# main_board.net
KiCad netlist of a schematic drawn in EAGLE
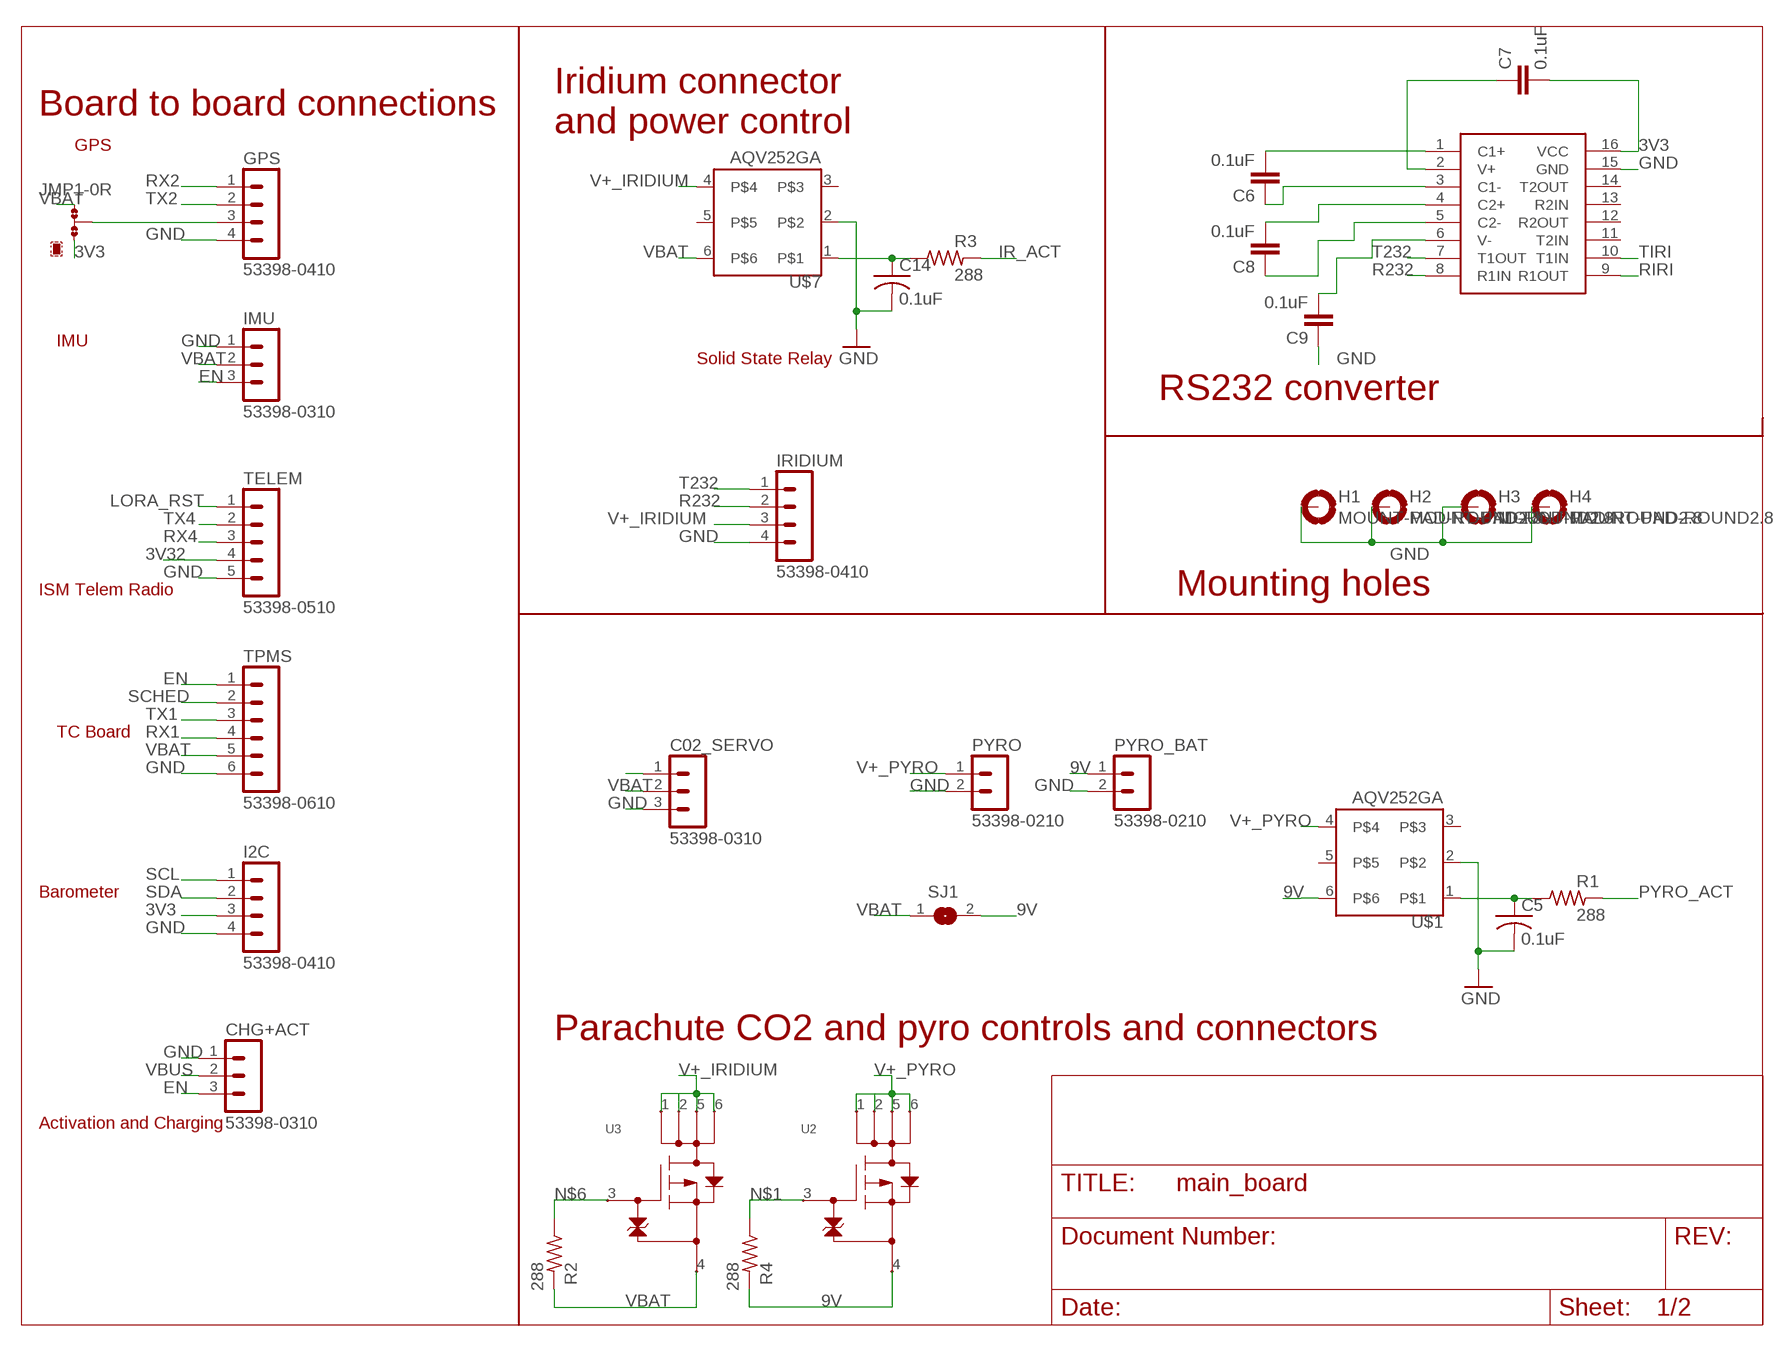
[diagram p0: schematic, sheet 1]
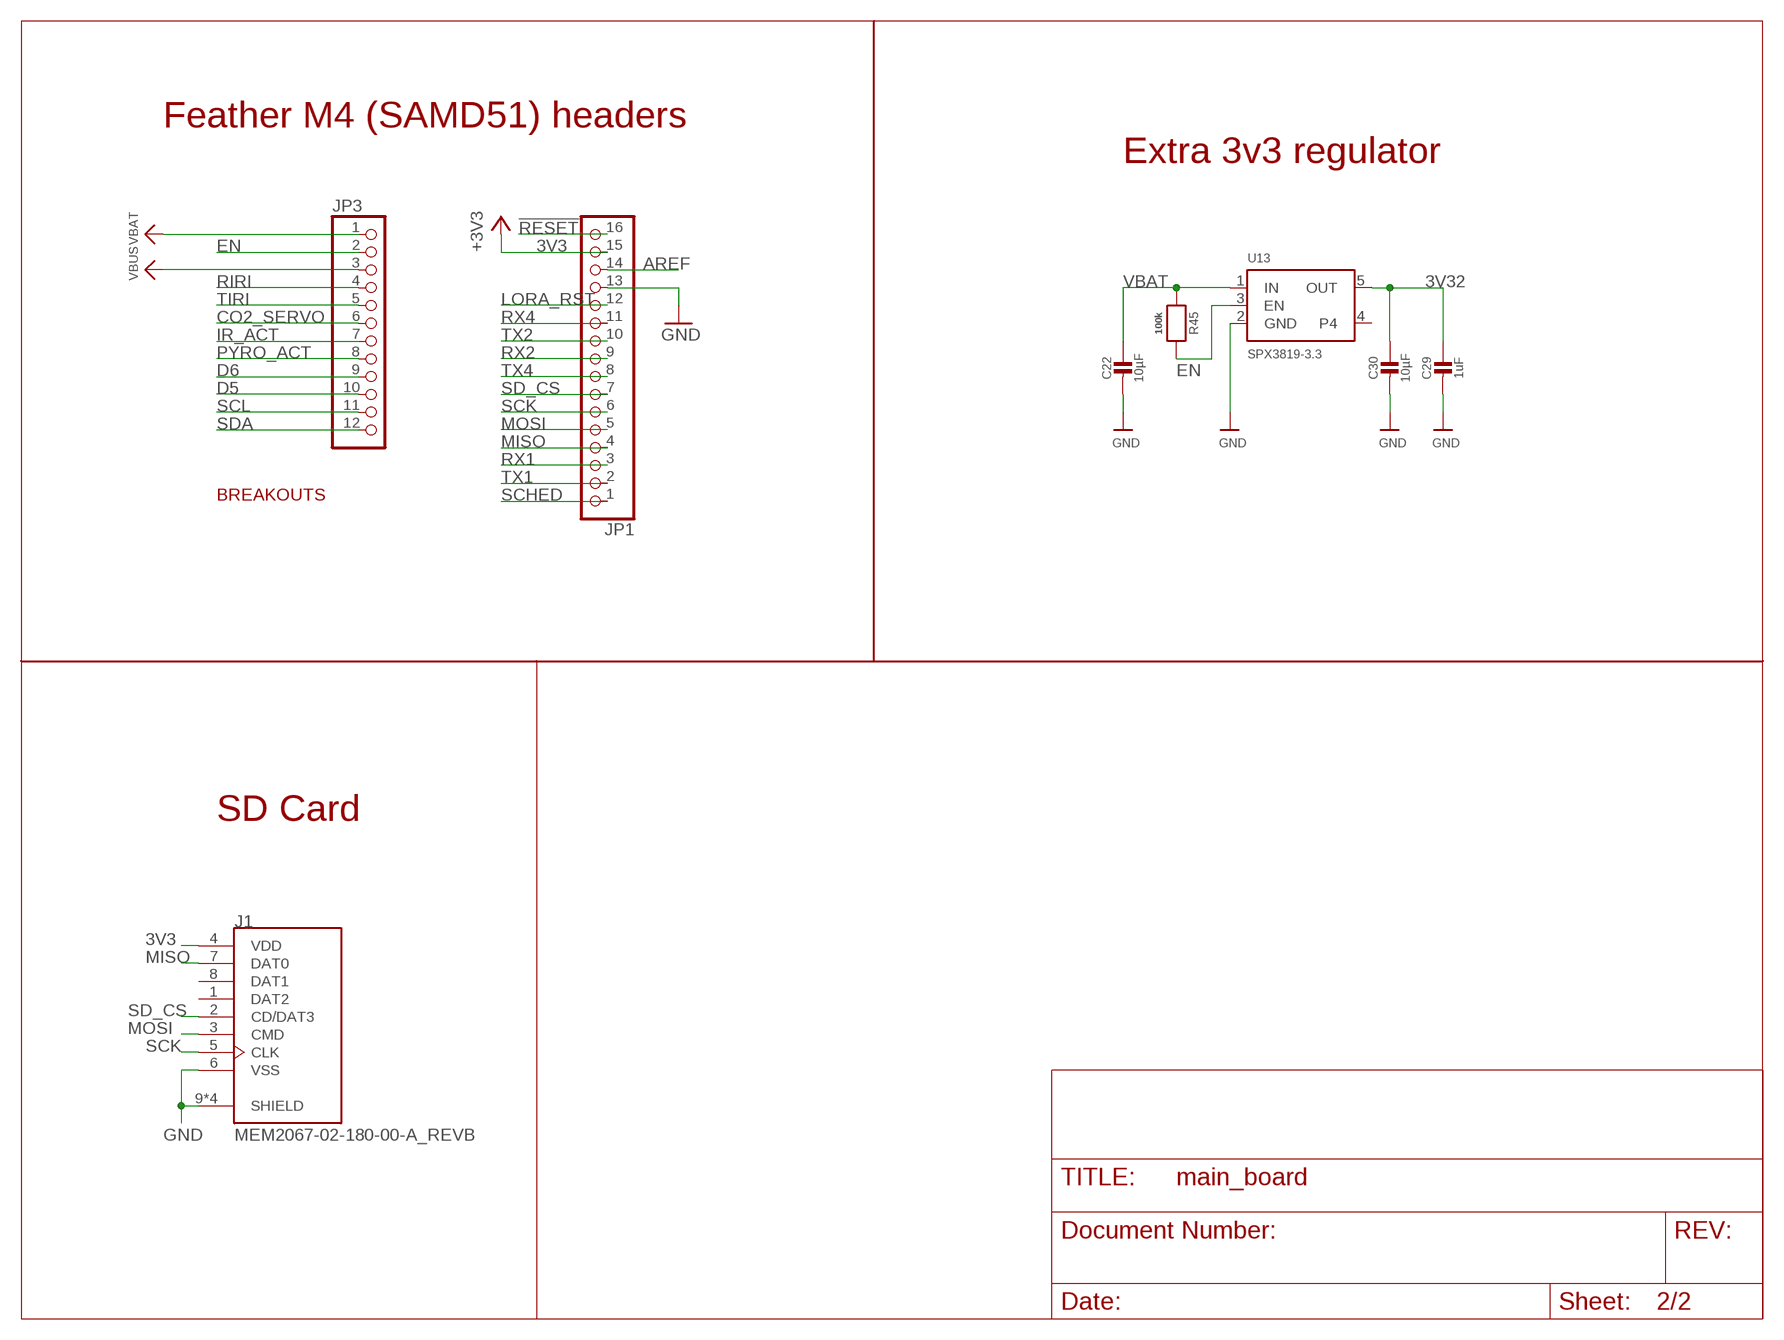
[diagram p1: schematic, sheet 2]

(export (version "E")
  (design (tool "Eeschema 10.0.6"))
  (components
    (comp (ref "C22")
      (value "10µF")
      (footprint "eagle-import:0805-NO")
      (libsource (lib "eagle-import") (part "CAP_CERAMIC0805-NOOUTLINE"))
    )
    (comp (ref "C29")
      (value "1uF")
      (footprint "eagle-import:0603-NO")
      (libsource (lib "eagle-import") (part "CAP_CERAMIC0603_NO"))
    )
    (comp (ref "C30")
      (value "10µF")
      (footprint "eagle-import:0805-NO")
      (libsource (lib "eagle-import") (part "CAP_CERAMIC0805-NOOUTLINE"))
    )
    (comp (ref "J1")
      (value "MEM2067-02-180-00-A_REVB")
      (footprint "eagle-import:GCT_MEM2067-02-180-00-A_REVB")
      (fields (field (name "MF") "Global Connector Technology") (field (name "MP") "MEM2067-02-180-00-A"))
      (libsource (lib "eagle-import") (part "MEM2067-02-180-00-A_REVB"))
    )
    (comp (ref "JP1")
      (value "HEADER-1X16ROUND")
      (footprint "eagle-import:1X16_ROUND")
      (libsource (lib "eagle-import") (part "HEADER-1X16ROUND"))
    )
    (comp (ref "JP3")
      (value "HEADER-1X12")
      (footprint "eagle-import:1X12_ROUND")
      (libsource (lib "eagle-import") (part "HEADER-1X12"))
    )
    (comp (ref "R45")
      (value "100k")
      (footprint "eagle-import:0603-NO")
      (libsource (lib "eagle-import") (part "RESISTOR_0603_NOOUT"))
    )
    (comp (ref "U13")
      (value "SPX3819-3.3")
      (footprint "eagle-import:SOT23-5")
      (libsource (lib "eagle-import") (part "VREG_SOT23-5"))
    )
    (comp (ref "C02_SERVO")
      (value "53398-0310")
      (footprint "eagle-import:53398-0310")
      (libsource (lib "eagle-import") (part "53398-0310"))
    )
    (comp (ref "C5")
      (value "0.1uF")
      (footprint "eagle-import:C0603")
      (libsource (lib "eagle-import") (part "C-USC0603"))
    )
    (comp (ref "C6")
      (value "0.1uF")
      (footprint "eagle-import:C0603")
      (libsource (lib "eagle-import") (part "C-EUC0603"))
    )
    (comp (ref "C7")
      (value "0.1uF")
      (footprint "eagle-import:C0603")
      (libsource (lib "eagle-import") (part "C-EUC0603"))
    )
    (comp (ref "C8")
      (value "0.1uF")
      (footprint "eagle-import:C0603")
      (libsource (lib "eagle-import") (part "C-EUC0603"))
    )
    (comp (ref "C9")
      (value "0.1uF")
      (footprint "eagle-import:C0603")
      (libsource (lib "eagle-import") (part "C-EUC0603"))
    )
    (comp (ref "C14")
      (value "0.1uF")
      (footprint "eagle-import:C0603")
      (libsource (lib "eagle-import") (part "C-USC0603"))
    )
    (comp (ref "CHG+ACT")
      (value "53398-0310")
      (footprint "eagle-import:53398-0310")
      (libsource (lib "eagle-import") (part "53398-0310"))
    )
    (comp (ref "GPS")
      (value "53398-0410")
      (footprint "eagle-import:53398-0410")
      (libsource (lib "eagle-import") (part "53398-0410"))
    )
    (comp (ref "H1")
      (value "MOUNT-PAD-ROUND2.8")
      (footprint "eagle-import:2,8-PAD")
      (libsource (lib "eagle-import") (part "MOUNT-PAD-ROUND2.8"))
    )
    (comp (ref "H2")
      (value "MOUNT-PAD-ROUND2.8")
      (footprint "eagle-import:2,8-PAD")
      (libsource (lib "eagle-import") (part "MOUNT-PAD-ROUND2.8"))
    )
    (comp (ref "H3")
      (value "MOUNT-PAD-ROUND2.8")
      (footprint "eagle-import:2,8-PAD")
      (libsource (lib "eagle-import") (part "MOUNT-PAD-ROUND2.8"))
    )
    (comp (ref "H4")
      (value "MOUNT-PAD-ROUND2.8")
      (footprint "eagle-import:2,8-PAD")
      (libsource (lib "eagle-import") (part "MOUNT-PAD-ROUND2.8"))
    )
    (comp (ref "I2C")
      (value "53398-0410")
      (footprint "eagle-import:53398-0410")
      (libsource (lib "eagle-import") (part "53398-0410"))
    )
    (comp (ref "IMU")
      (value "53398-0310")
      (footprint "eagle-import:53398-0310")
      (libsource (lib "eagle-import") (part "53398-0310"))
    )
    (comp (ref "IRIDIUM")
      (value "53398-0410")
      (footprint "eagle-import:53398-0410")
      (libsource (lib "eagle-import") (part "53398-0410"))
    )
    (comp (ref "JMP1")
      (value "0R-JUMPA")
      (footprint "eagle-import:A0R-JMP")
      (libsource (lib "eagle-import") (part "0R-JUMPA"))
    )
    (comp (ref "PYRO")
      (value "53398-0210")
      (footprint "eagle-import:53398-0210")
      (libsource (lib "eagle-import") (part "53398-0210"))
    )
    (comp (ref "PYRO_BAT")
      (value "53398-0210")
      (footprint "eagle-import:53398-0210")
      (libsource (lib "eagle-import") (part "53398-0210"))
    )
    (comp (ref "R1")
      (value "288")
      (footprint "eagle-import:R0603")
      (libsource (lib "eagle-import") (part "R-US_R0603"))
    )
    (comp (ref "R2")
      (value "288")
      (footprint "eagle-import:R0603")
      (libsource (lib "eagle-import") (part "R-US_R0603"))
    )
    (comp (ref "R3")
      (value "288")
      (footprint "eagle-import:R0603")
      (libsource (lib "eagle-import") (part "R-US_R0603"))
    )
    (comp (ref "R4")
      (value "288")
      (footprint "eagle-import:R0603")
      (libsource (lib "eagle-import") (part "R-US_R0603"))
    )
    (comp (ref "SJ1") (value "SJ") (footprint "eagle-import:SJ") (libsource (lib "eagle-import") (part "SJ")))
    (comp (ref "TELEM")
      (value "53398-0510")
      (footprint "eagle-import:53398-0510")
      (libsource (lib "eagle-import") (part "53398-0510"))
    )
    (comp (ref "TPMS")
      (value "53398-0610")
      (footprint "eagle-import:53398-0610")
      (libsource (lib "eagle-import") (part "53398-0610"))
    )
    (comp (ref "U$1")
      (value "AQV252GA")
      (footprint "eagle-import:DIP6")
      (libsource (lib "eagle-import") (part "AQV252GA"))
    )
    (comp (ref "U$2")
      (value "UM3232EEAE")
      (footprint "eagle-import:RQ_16_ADI")
      (libsource (lib "eagle-import") (part "UM3232EEAE"))
    )
    (comp (ref "U$7")
      (value "AQV252GA")
      (footprint "eagle-import:DIP6")
      (libsource (lib "eagle-import") (part "AQV252GA"))
    )
    (comp (ref "U2")
      (value "SSM6J414TU")
      (footprint "eagle-import:UF6_TOS")
      (fields (field (name "COPYRIGHT") "Copyright (C) 2021 Ultra Librarian. All rights reserved."))
      (libsource (lib "eagle-import") (part "SSM6J414TU"))
    )
    (comp (ref "U3")
      (value "SSM6J414TU")
      (footprint "eagle-import:UF6_TOS")
      (fields (field (name "COPYRIGHT") "Copyright (C) 2021 Ultra Librarian. All rights reserved."))
      (libsource (lib "eagle-import") (part "SSM6J414TU"))
    )
  )
  (nets
    (net (code "1") (name "3V3") (class "Default")
      (node (ref "C7") (pin "2") (pinfunction "2_2") (pintype "passive"))
      (node (ref "I2C") (pin "3") (pinfunction "3_3") (pintype "passive"))
      (node (ref "J1") (pin "4") (pinfunction "VDD_4") (pintype "power_in"))
      (node (ref "JMP1") (pin "3") (pinfunction "3_3") (pintype "passive"))
      (node (ref "JP1") (pin "15") (pinfunction "15_15") (pintype "passive"))
      (node (ref "U$2") (pin "16") (pinfunction "VCC_16") (pintype "bidirectional"))
    )
    (net (code "2") (name "3V32") (class "Default")
      (node (ref "C29") (pin "1") (pinfunction "1_1") (pintype "passive"))
      (node (ref "C30") (pin "1") (pinfunction "1_1") (pintype "passive"))
      (node (ref "TELEM") (pin "4") (pinfunction "4_4") (pintype "passive"))
      (node (ref "U13") (pin "5") (pinfunction "OUT_5") (pintype "power_in"))
    )
    (net (code "3") (name "9V") (class "Default")
      (node (ref "PYRO_BAT") (pin "1") (pinfunction "1_1") (pintype "passive"))
      (node (ref "R4") (pin "2") (pinfunction "2_2") (pintype "passive"))
      (node (ref "SJ1") (pin "2") (pinfunction "2_2") (pintype "passive"))
      (node (ref "U$1") (pin "6") (pinfunction "P$6_6") (pintype "bidirectional"))
      (node (ref "U2") (pin "4") (pinfunction "4_4") (pintype "passive"))
    )
    (net (code "4") (name "AREF") (class "Default")
      (node (ref "JP1") (pin "14") (pinfunction "14_14") (pintype "passive"))
    )
    (net (code "5") (name "CO2_SERVO") (class "Default")
      (node (ref "C02_SERVO") (pin "1") (pinfunction "1_1") (pintype "passive"))
      (node (ref "JP3") (pin "6") (pinfunction "6_6") (pintype "passive"))
    )
    (net (code "6") (name "D5") (class "Default")
      (node (ref "JP3") (pin "10") (pinfunction "10_10") (pintype "passive"))
    )
    (net (code "7") (name "D6") (class "Default")
      (node (ref "JP3") (pin "9") (pinfunction "9_9") (pintype "passive"))
    )
    (net (code "8") (name "EN") (class "Default")
      (node (ref "CHG+ACT") (pin "3") (pinfunction "3_3") (pintype "passive"))
      (node (ref "IMU") (pin "3") (pinfunction "3_3") (pintype "passive"))
      (node (ref "JP3") (pin "2") (pinfunction "2_2") (pintype "passive"))
      (node (ref "R45") (pin "2") (pinfunction "2_2") (pintype "passive"))
      (node (ref "TPMS") (pin "1") (pinfunction "1_1") (pintype "passive"))
      (node (ref "U13") (pin "3") (pinfunction "EN_3") (pintype "input"))
    )
    (net (code "9") (name "GND") (class "Default")
      (node (ref "C02_SERVO") (pin "3") (pinfunction "3_3") (pintype "passive"))
      (node (ref "C14") (pin "2") (pinfunction "2_2") (pintype "passive"))
      (node (ref "C22") (pin "2") (pinfunction "2_2") (pintype "passive"))
      (node (ref "C29") (pin "2") (pinfunction "2_2") (pintype "passive"))
      (node (ref "C30") (pin "2") (pinfunction "2_2") (pintype "passive"))
      (node (ref "C5") (pin "2") (pinfunction "2_2") (pintype "passive"))
      (node (ref "C9") (pin "1") (pinfunction "1_1") (pintype "passive"))
      (node (ref "CHG+ACT") (pin "1") (pinfunction "1_1") (pintype "passive"))
      (node (ref "GPS") (pin "4") (pinfunction "4_4") (pintype "passive"))
      (node (ref "H1") (pin "B2,8") (pinfunction "MOUNT_B2,8") (pintype "passive"))
      (node (ref "H2") (pin "B2,8") (pinfunction "MOUNT_B2,8") (pintype "passive"))
      (node (ref "H3") (pin "B2,8") (pinfunction "MOUNT_B2,8") (pintype "passive"))
      (node (ref "H4") (pin "B2,8") (pinfunction "MOUNT_B2,8") (pintype "passive"))
      (node (ref "I2C") (pin "4") (pinfunction "4_4") (pintype "passive"))
      (node (ref "IMU") (pin "1") (pinfunction "1_1") (pintype "passive"))
      (node (ref "IRIDIUM") (pin "4") (pinfunction "4_4") (pintype "passive"))
      (node (ref "J1") (pin "10") (pinfunction "SHIELD_10") (pintype "passive"))
      (node (ref "J1") (pin "11") (pinfunction "SHIELD_11") (pintype "passive"))
      (node (ref "J1") (pin "12") (pinfunction "SHIELD_12") (pintype "passive"))
      (node (ref "J1") (pin "6") (pinfunction "VSS_6") (pintype "power_in"))
      (node (ref "J1") (pin "9") (pinfunction "SHIELD_9") (pintype "passive"))
      (node (ref "JP1") (pin "13") (pinfunction "13_13") (pintype "passive"))
      (node (ref "PYRO") (pin "2") (pinfunction "2_2") (pintype "passive"))
      (node (ref "PYRO_BAT") (pin "2") (pinfunction "2_2") (pintype "passive"))
      (node (ref "TELEM") (pin "5") (pinfunction "5_5") (pintype "passive"))
      (node (ref "TPMS") (pin "6") (pinfunction "6_6") (pintype "passive"))
      (node (ref "U$1") (pin "2") (pinfunction "P$2_2") (pintype "bidirectional"))
      (node (ref "U$2") (pin "15") (pinfunction "GND_15") (pintype "bidirectional"))
      (node (ref "U$7") (pin "2") (pinfunction "P$2_2") (pintype "bidirectional"))
      (node (ref "U13") (pin "2") (pinfunction "GND_2") (pintype "power_in"))
    )
    (net (code "10") (name "IR_ACT") (class "Default")
      (node (ref "JP3") (pin "7") (pinfunction "7_7") (pintype "passive"))
      (node (ref "R3") (pin "2") (pinfunction "2_2") (pintype "passive"))
    )
    (net (code "11") (name "LORA_RST") (class "Default")
      (node (ref "JP1") (pin "12") (pinfunction "12_12") (pintype "passive"))
      (node (ref "TELEM") (pin "1") (pinfunction "1_1") (pintype "passive"))
    )
    (net (code "12") (name "MISO") (class "Default")
      (node (ref "J1") (pin "7") (pinfunction "DAT0_7") (pintype "bidirectional"))
      (node (ref "JP1") (pin "4") (pinfunction "4_4") (pintype "passive"))
    )
    (net (code "13") (name "MOSI") (class "Default")
      (node (ref "J1") (pin "3") (pinfunction "CMD_3") (pintype "bidirectional"))
      (node (ref "JP1") (pin "5") (pinfunction "5_5") (pintype "passive"))
    )
    (net (code "14") (name "N$1") (class "Default")
      (node (ref "C5") (pin "1") (pinfunction "1_1") (pintype "passive"))
      (node (ref "R1") (pin "1") (pinfunction "1_1") (pintype "passive"))
      (node (ref "R4") (pin "1") (pinfunction "1_1") (pintype "passive"))
      (node (ref "U$1") (pin "1") (pinfunction "P$1_1") (pintype "bidirectional"))
      (node (ref "U2") (pin "3") (pinfunction "3_3") (pintype "passive"))
    )
    (net (code "15") (name "N$6") (class "Default")
      (node (ref "C14") (pin "1") (pinfunction "1_1") (pintype "passive"))
      (node (ref "R2") (pin "1") (pinfunction "1_1") (pintype "passive"))
      (node (ref "R3") (pin "1") (pinfunction "1_1") (pintype "passive"))
      (node (ref "U$7") (pin "1") (pinfunction "P$1_1") (pintype "bidirectional"))
      (node (ref "U3") (pin "3") (pinfunction "3_3") (pintype "passive"))
    )
    (net (code "16") (name "Net-(GPS-Pad3)") (class "Default")
      (node (ref "GPS") (pin "3") (pinfunction "3_3") (pintype "passive"))
      (node (ref "JMP1") (pin "2") (pinfunction "2_2") (pintype "passive"))
    )
    (net (code "17") (name "Net-(U$2-C1+)") (class "Default")
      (node (ref "C6") (pin "2") (pinfunction "2_2") (pintype "passive"))
      (node (ref "U$2") (pin "1") (pinfunction "C1+_1") (pintype "bidirectional"))
    )
    (net (code "18") (name "Net-(U$2-C1-)") (class "Default")
      (node (ref "C6") (pin "1") (pinfunction "1_1") (pintype "passive"))
      (node (ref "U$2") (pin "3") (pinfunction "C1-_3") (pintype "bidirectional"))
    )
    (net (code "19") (name "Net-(U$2-C2+)") (class "Default")
      (node (ref "C8") (pin "2") (pinfunction "2_2") (pintype "passive"))
      (node (ref "U$2") (pin "4") (pinfunction "C2+_4") (pintype "bidirectional"))
    )
    (net (code "20") (name "Net-(U$2-C2-)") (class "Default")
      (node (ref "C8") (pin "1") (pinfunction "1_1") (pintype "passive"))
      (node (ref "U$2") (pin "5") (pinfunction "C2-_5") (pintype "bidirectional"))
    )
    (net (code "21") (name "Net-(U$2-V+)") (class "Default")
      (node (ref "C7") (pin "1") (pinfunction "1_1") (pintype "passive"))
      (node (ref "U$2") (pin "2") (pinfunction "V+_2") (pintype "bidirectional"))
    )
    (net (code "22") (name "Net-(U$2-V-)") (class "Default")
      (node (ref "C9") (pin "2") (pinfunction "2_2") (pintype "passive"))
      (node (ref "U$2") (pin "6") (pinfunction "V-_6") (pintype "bidirectional"))
    )
    (net (code "23") (name "PYRO_ACT") (class "Default")
      (node (ref "JP3") (pin "8") (pinfunction "8_8") (pintype "passive"))
      (node (ref "R1") (pin "2") (pinfunction "2_2") (pintype "passive"))
    )
    (net (code "24") (name "R232") (class "Default")
      (node (ref "IRIDIUM") (pin "2") (pinfunction "2_2") (pintype "passive"))
      (node (ref "U$2") (pin "8") (pinfunction "R1IN_8") (pintype "bidirectional"))
    )
    (net (code "25") (name "RIRI") (class "Default")
      (node (ref "JP3") (pin "4") (pinfunction "4_4") (pintype "passive"))
      (node (ref "U$2") (pin "9") (pinfunction "R1OUT_9") (pintype "bidirectional"))
    )
    (net (code "26") (name "RX1") (class "Default")
      (node (ref "JP1") (pin "3") (pinfunction "3_3") (pintype "passive"))
      (node (ref "TPMS") (pin "4") (pinfunction "4_4") (pintype "passive"))
    )
    (net (code "27") (name "RX2") (class "Default")
      (node (ref "GPS") (pin "1") (pinfunction "1_1") (pintype "passive"))
      (node (ref "JP1") (pin "9") (pinfunction "9_9") (pintype "passive"))
    )
    (net (code "28") (name "RX4") (class "Default")
      (node (ref "JP1") (pin "11") (pinfunction "11_11") (pintype "passive"))
      (node (ref "TELEM") (pin "3") (pinfunction "3_3") (pintype "passive"))
    )
    (net (code "29") (name "SCHED") (class "Default")
      (node (ref "JP1") (pin "1") (pinfunction "1_1") (pintype "passive"))
      (node (ref "TPMS") (pin "2") (pinfunction "2_2") (pintype "passive"))
    )
    (net (code "30") (name "SCK") (class "Default")
      (node (ref "J1") (pin "5") (pinfunction "CLK_5") (pintype "bidirectional"))
      (node (ref "JP1") (pin "6") (pinfunction "6_6") (pintype "passive"))
    )
    (net (code "31") (name "SCL") (class "Default")
      (node (ref "I2C") (pin "1") (pinfunction "1_1") (pintype "passive"))
      (node (ref "JP3") (pin "11") (pinfunction "11_11") (pintype "passive"))
    )
    (net (code "32") (name "SDA") (class "Default")
      (node (ref "I2C") (pin "2") (pinfunction "2_2") (pintype "passive"))
      (node (ref "JP3") (pin "12") (pinfunction "12_12") (pintype "passive"))
    )
    (net (code "33") (name "SD_CS") (class "Default")
      (node (ref "J1") (pin "2") (pinfunction "CD/DAT3_2") (pintype "bidirectional"))
      (node (ref "JP1") (pin "7") (pinfunction "7_7") (pintype "passive"))
    )
    (net (code "34") (name "T232") (class "Default")
      (node (ref "IRIDIUM") (pin "1") (pinfunction "1_1") (pintype "passive"))
      (node (ref "U$2") (pin "7") (pinfunction "T1OUT_7") (pintype "bidirectional"))
    )
    (net (code "35") (name "TIRI") (class "Default")
      (node (ref "JP3") (pin "5") (pinfunction "5_5") (pintype "passive"))
      (node (ref "U$2") (pin "10") (pinfunction "T1IN_10") (pintype "bidirectional"))
    )
    (net (code "36") (name "TX1") (class "Default")
      (node (ref "JP1") (pin "2") (pinfunction "2_2") (pintype "passive"))
      (node (ref "TPMS") (pin "3") (pinfunction "3_3") (pintype "passive"))
    )
    (net (code "37") (name "TX2") (class "Default")
      (node (ref "GPS") (pin "2") (pinfunction "2_2") (pintype "passive"))
      (node (ref "JP1") (pin "10") (pinfunction "10_10") (pintype "passive"))
    )
    (net (code "38") (name "TX4") (class "Default")
      (node (ref "JP1") (pin "8") (pinfunction "8_8") (pintype "passive"))
      (node (ref "TELEM") (pin "2") (pinfunction "2_2") (pintype "passive"))
    )
    (net (code "39") (name "V+_IRIDIUM") (class "Default")
      (node (ref "IRIDIUM") (pin "3") (pinfunction "3_3") (pintype "passive"))
      (node (ref "U$7") (pin "4") (pinfunction "P$4_4") (pintype "bidirectional"))
      (node (ref "U3") (pin "1") (pinfunction "1_1") (pintype "passive"))
      (node (ref "U3") (pin "2") (pinfunction "2_2") (pintype "passive"))
      (node (ref "U3") (pin "5") (pinfunction "5_5") (pintype "passive"))
      (node (ref "U3") (pin "6") (pinfunction "6_6") (pintype "passive"))
    )
    (net (code "40") (name "V+_PYRO") (class "Default")
      (node (ref "PYRO") (pin "1") (pinfunction "1_1") (pintype "passive"))
      (node (ref "U$1") (pin "4") (pinfunction "P$4_4") (pintype "bidirectional"))
      (node (ref "U2") (pin "1") (pinfunction "1_1") (pintype "passive"))
      (node (ref "U2") (pin "2") (pinfunction "2_2") (pintype "passive"))
      (node (ref "U2") (pin "5") (pinfunction "5_5") (pintype "passive"))
      (node (ref "U2") (pin "6") (pinfunction "6_6") (pintype "passive"))
    )
    (net (code "41") (name "VBAT") (class "Default")
      (node (ref "C02_SERVO") (pin "2") (pinfunction "2_2") (pintype "passive"))
      (node (ref "C22") (pin "1") (pinfunction "1_1") (pintype "passive"))
      (node (ref "IMU") (pin "2") (pinfunction "2_2") (pintype "passive"))
      (node (ref "JMP1") (pin "1") (pinfunction "1_1") (pintype "passive"))
      (node (ref "JP3") (pin "1") (pinfunction "1_1") (pintype "passive"))
      (node (ref "R2") (pin "2") (pinfunction "2_2") (pintype "passive"))
      (node (ref "R45") (pin "1") (pinfunction "1_1") (pintype "passive"))
      (node (ref "SJ1") (pin "1") (pinfunction "1_1") (pintype "passive"))
      (node (ref "TPMS") (pin "5") (pinfunction "5_5") (pintype "passive"))
      (node (ref "U$7") (pin "6") (pinfunction "P$6_6") (pintype "bidirectional"))
      (node (ref "U13") (pin "1") (pinfunction "IN_1") (pintype "power_in"))
      (node (ref "U3") (pin "4") (pinfunction "4_4") (pintype "passive"))
    )
    (net (code "42") (name "VBUS") (class "Default")
      (node (ref "CHG+ACT") (pin "2") (pinfunction "2_2") (pintype "passive"))
      (node (ref "JP3") (pin "3") (pinfunction "3_3") (pintype "passive"))
    )
    (net (code "43") (name "unconnected-(J1-DAT1-Pad8)") (class "Default")
      (node (ref "J1") (pin "8") (pinfunction "DAT1_8") (pintype "bidirectional"))
    )
    (net (code "44") (name "unconnected-(J1-DAT2-Pad1)") (class "Default")
      (node (ref "J1") (pin "1") (pinfunction "DAT2_1") (pintype "bidirectional"))
    )
    (net (code "45") (name "unconnected-(U$1-P$3-Pad3)") (class "Default")
      (node (ref "U$1") (pin "3") (pinfunction "P$3_3") (pintype "bidirectional"))
    )
    (net (code "46") (name "unconnected-(U$1-P$5-Pad5)") (class "Default")
      (node (ref "U$1") (pin "5") (pinfunction "P$5_5") (pintype "bidirectional"))
    )
    (net (code "47") (name "unconnected-(U$2-R2IN-Pad13)") (class "Default")
      (node (ref "U$2") (pin "13") (pinfunction "R2IN_13") (pintype "bidirectional"))
    )
    (net (code "48") (name "unconnected-(U$2-R2OUT-Pad12)") (class "Default")
      (node (ref "U$2") (pin "12") (pinfunction "R2OUT_12") (pintype "bidirectional"))
    )
    (net (code "49") (name "unconnected-(U$2-T2IN-Pad11)") (class "Default")
      (node (ref "U$2") (pin "11") (pinfunction "T2IN_11") (pintype "bidirectional"))
    )
    (net (code "50") (name "unconnected-(U$2-T2OUT-Pad14)") (class "Default")
      (node (ref "U$2") (pin "14") (pinfunction "T2OUT_14") (pintype "bidirectional"))
    )
    (net (code "51") (name "unconnected-(U$7-P$3-Pad3)") (class "Default")
      (node (ref "U$7") (pin "3") (pinfunction "P$3_3") (pintype "bidirectional"))
    )
    (net (code "52") (name "unconnected-(U$7-P$5-Pad5)") (class "Default")
      (node (ref "U$7") (pin "5") (pinfunction "P$5_5") (pintype "bidirectional"))
    )
    (net (code "53") (name "unconnected-(U13-P4-Pad4)") (class "Default")
      (node (ref "U13") (pin "4") (pinfunction "P4_4") (pintype "bidirectional"))
    )
    (net (code "54") (name "~{RESET}") (class "Default")
      (node (ref "JP1") (pin "16") (pinfunction "16_16") (pintype "passive"))
    )
  )
)
